# ERpcukSD.net
KiCad netlist of a schematic drawn in EAGLE
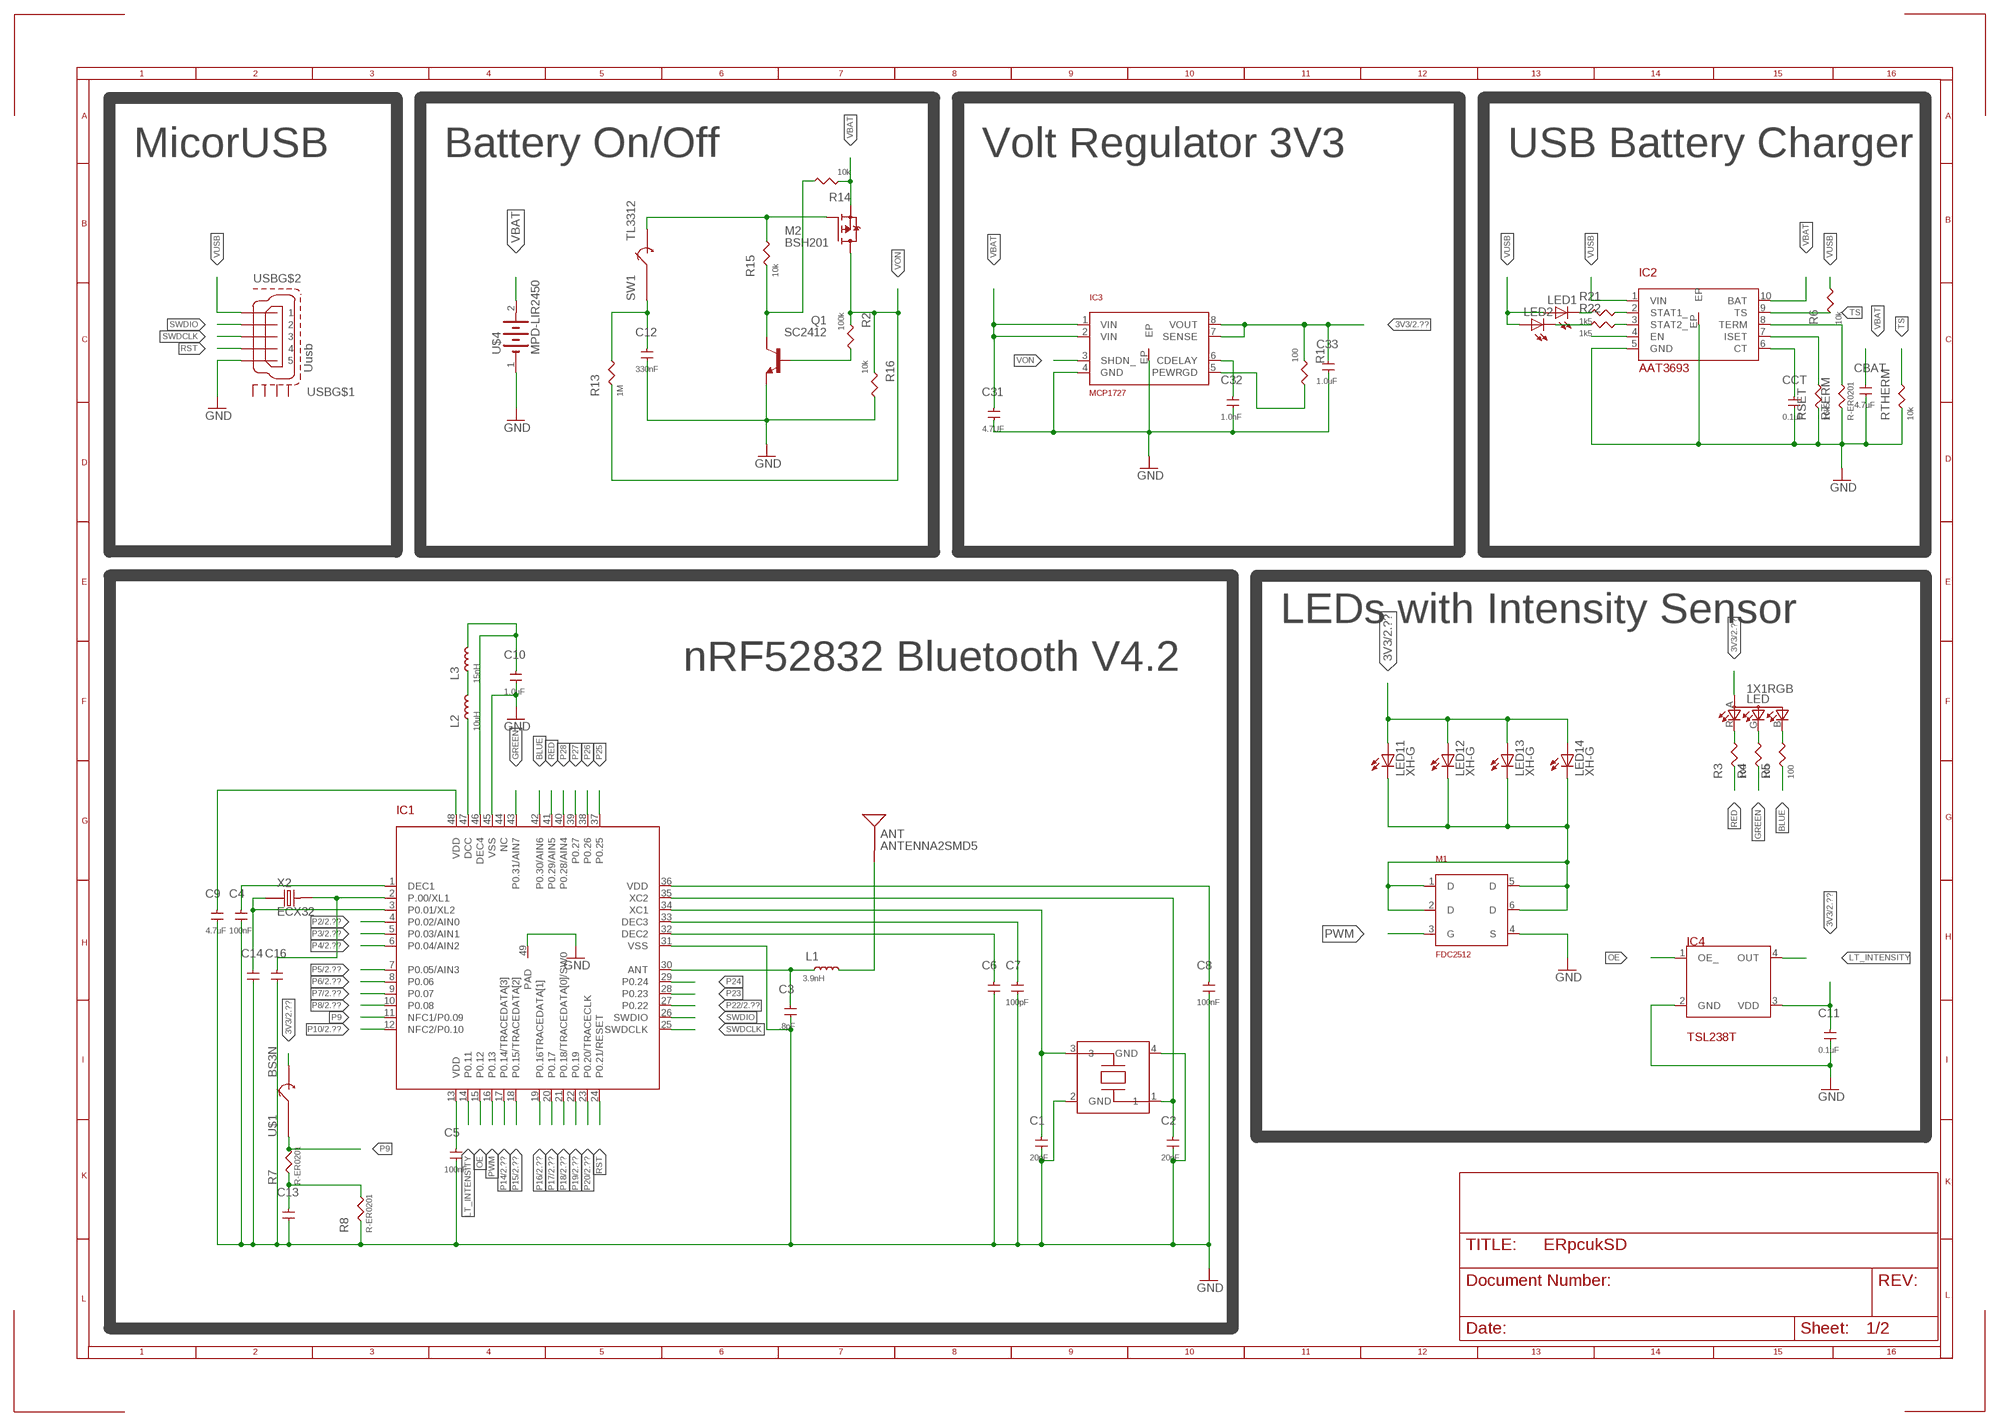
[diagram p0: schematic, sheet 1]
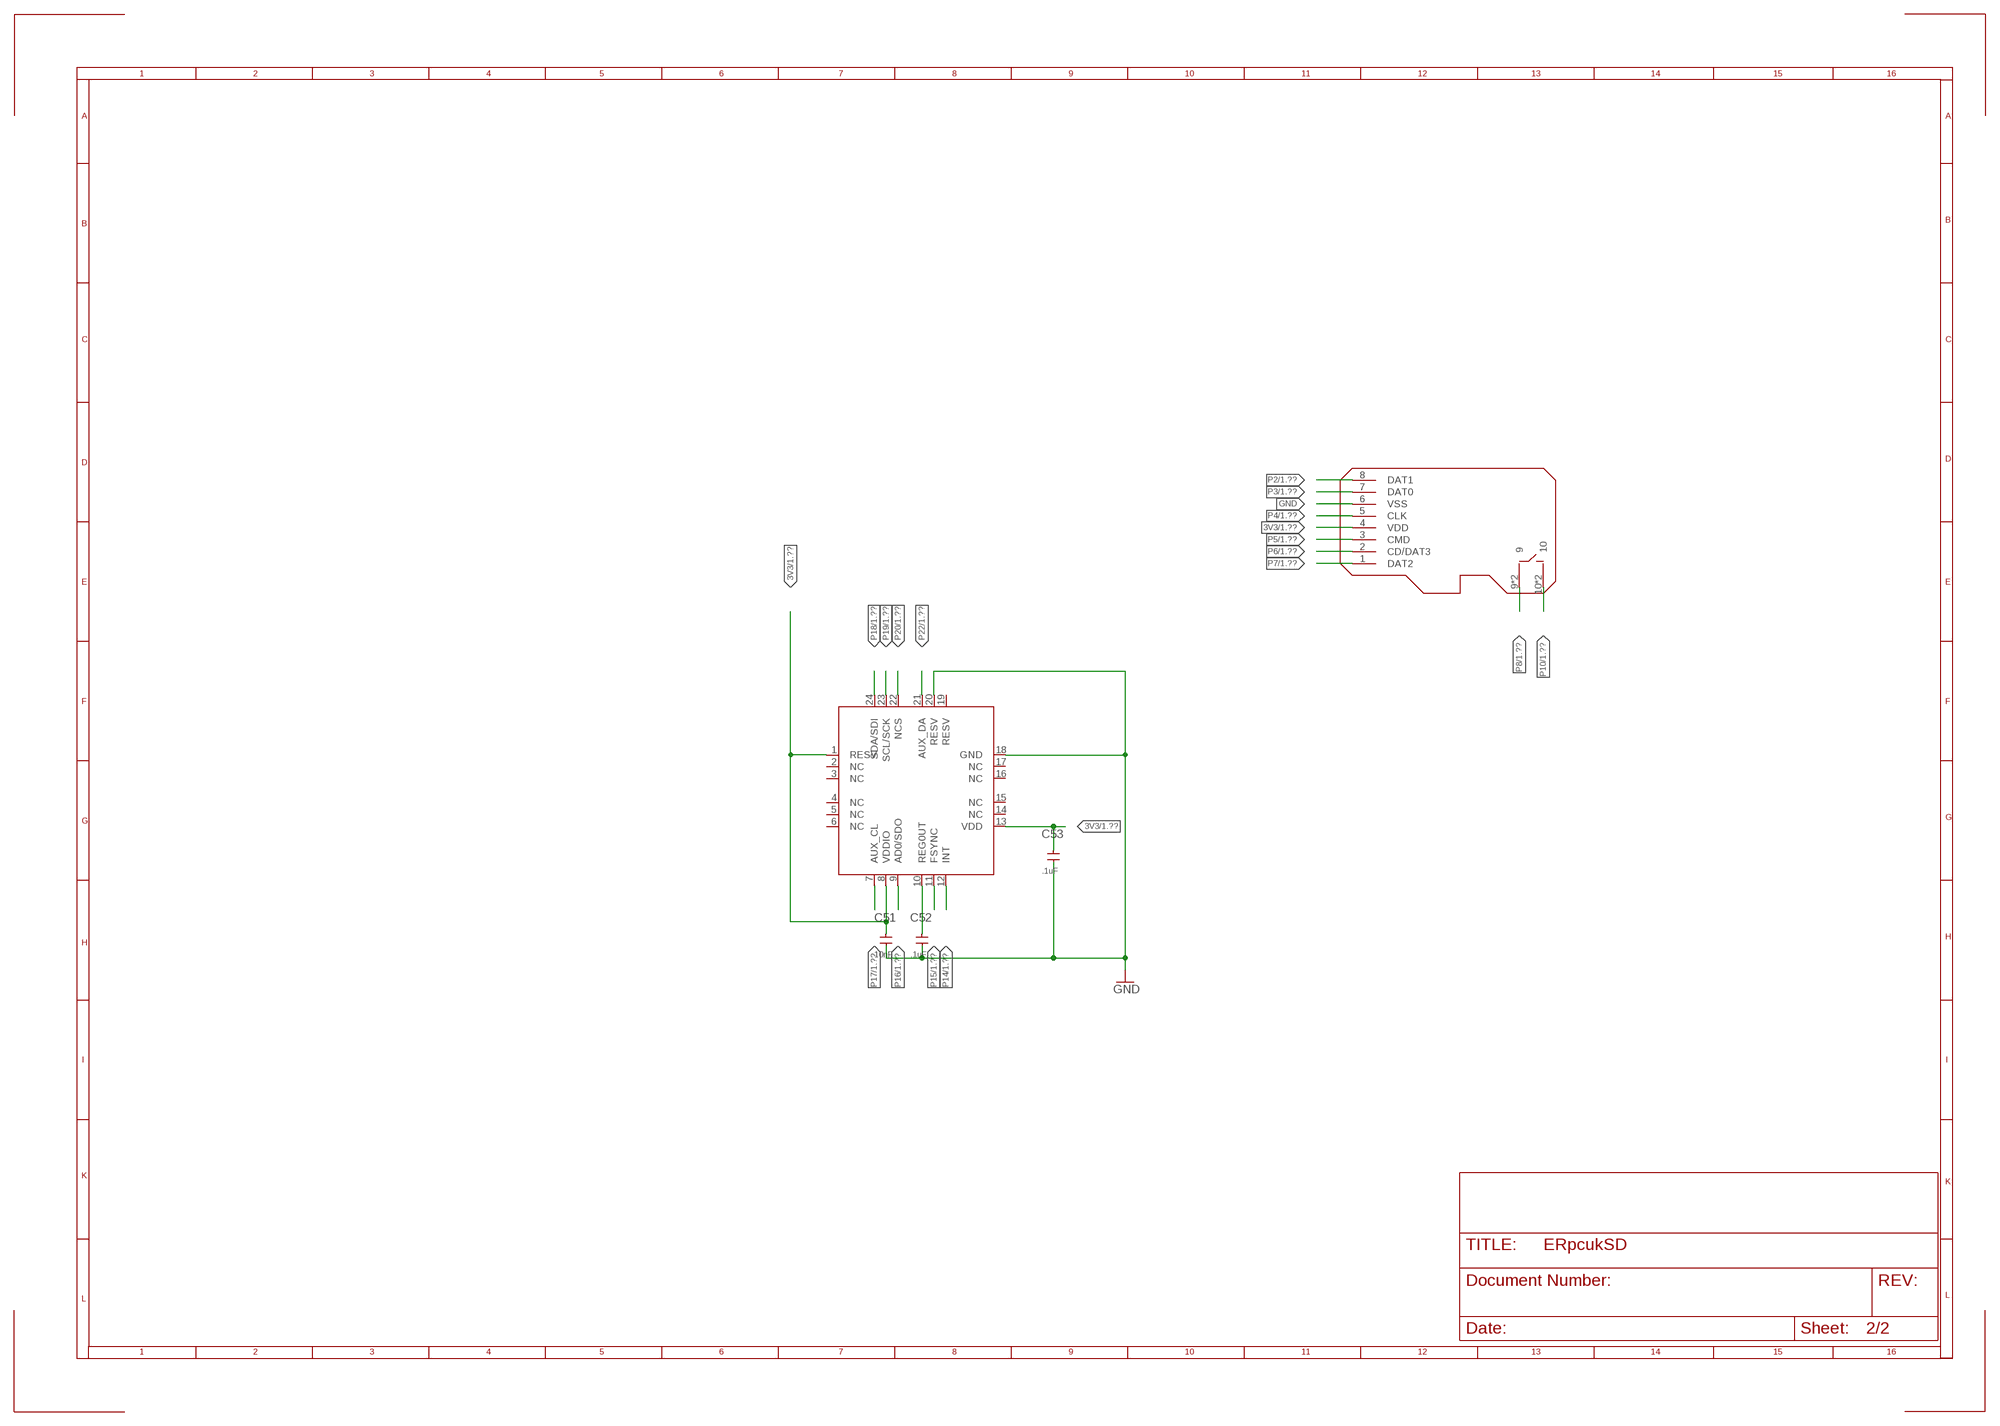
[diagram p1: schematic, sheet 2]

(export (version "E")
  (design (tool "Eeschema 10.0.6"))
  (components
    (comp (ref "C51")
      (value "10nF")
      (footprint "eagle-import:C0201")
      (libsource (lib "eagle-import") (part "C-ER201"))
    )
    (comp (ref "C52")
      (value ".1uF")
      (footprint "eagle-import:C0201")
      (libsource (lib "eagle-import") (part "C-ER201"))
    )
    (comp (ref "C53")
      (value ".1uF")
      (footprint "eagle-import:C0201")
      (libsource (lib "eagle-import") (part "C-ER201"))
    )
    (comp (ref "IC5")
      (value "MPU9250")
      (footprint "eagle-import:3X3_24_QFN_CORRECTED")
      (libsource (lib "eagle-import") (part "MPU9250_CORRECTED"))
    )
    (comp (ref "U$2")
      (value "MICROSD")
      (footprint "eagle-import:MICROSD")
      (libsource (lib "eagle-import") (part "MICROSD"))
    )
    (comp (ref "ANT")
      (value "ANTENNA2SMD5")
      (footprint "eagle-import:ANTENNA-CHIP5")
      (libsource (lib "eagle-import") (part "ANTENNA2SMD5"))
    )
    (comp (ref "C1")
      (value "20pF")
      (footprint "eagle-import:C0201")
      (libsource (lib "eagle-import") (part "C-ER201"))
    )
    (comp (ref "C2")
      (value "20pF")
      (footprint "eagle-import:C0201")
      (libsource (lib "eagle-import") (part "C-ER201"))
    )
    (comp (ref "C3")
      (value ".8pF")
      (footprint "eagle-import:C0201")
      (libsource (lib "eagle-import") (part "C-ER201"))
    )
    (comp (ref "C4")
      (value "100nF")
      (footprint "eagle-import:C0201")
      (libsource (lib "eagle-import") (part "C-ER201"))
    )
    (comp (ref "C5")
      (value "100nF")
      (footprint "eagle-import:C0201")
      (libsource (lib "eagle-import") (part "C-ER201"))
    )
    (comp (ref "C6")
      (value "C-ER201")
      (footprint "eagle-import:C0201")
      (libsource (lib "eagle-import") (part "C-ER201"))
    )
    (comp (ref "C7")
      (value "100pF")
      (footprint "eagle-import:C0201")
      (libsource (lib "eagle-import") (part "C-ER201"))
    )
    (comp (ref "C8")
      (value "100nF")
      (footprint "eagle-import:C0201")
      (libsource (lib "eagle-import") (part "C-ER201"))
    )
    (comp (ref "C9")
      (value "4.7uF")
      (footprint "eagle-import:C0402")
      (libsource (lib "eagle-import") (part "C-ERC0402"))
    )
    (comp (ref "C10")
      (value "1.0uF")
      (footprint "eagle-import:C0201")
      (libsource (lib "eagle-import") (part "C-ER201"))
    )
    (comp (ref "C11")
      (value "0.1uF")
      (footprint "eagle-import:C0201")
      (libsource (lib "eagle-import") (part "C-ER201"))
    )
    (comp (ref "C12")
      (value "330nF")
      (footprint "eagle-import:C0201")
      (libsource (lib "eagle-import") (part "C-ER201"))
    )
    (comp (ref "C13")
      (value "C-ER201")
      (footprint "eagle-import:C0201")
      (libsource (lib "eagle-import") (part "C-ER201"))
    )
    (comp (ref "C14")
      (value "C-ER201")
      (footprint "eagle-import:C0201")
      (libsource (lib "eagle-import") (part "C-ER201"))
    )
    (comp (ref "C16")
      (value "C-ER201")
      (footprint "eagle-import:C0201")
      (libsource (lib "eagle-import") (part "C-ER201"))
    )
    (comp (ref "C31")
      (value "4.7UF")
      (footprint "eagle-import:C0402")
      (libsource (lib "eagle-import") (part "C-ERC0402"))
    )
    (comp (ref "C32")
      (value "1.0nF")
      (footprint "eagle-import:C0201")
      (libsource (lib "eagle-import") (part "C-ER201"))
    )
    (comp (ref "C33")
      (value "1.0uF")
      (footprint "eagle-import:C0201")
      (libsource (lib "eagle-import") (part "C-ER201"))
    )
    (comp (ref "CBAT")
      (value "4.7uF")
      (footprint "eagle-import:C0402")
      (libsource (lib "eagle-import") (part "C-ERC0402"))
    )
    (comp (ref "CCT")
      (value "0.1uF")
      (footprint "eagle-import:C0201")
      (libsource (lib "eagle-import") (part "C-ER201"))
    )
    (comp (ref "IC1")
      (value "NRF52832")
      (footprint "eagle-import:QFN48")
      (libsource (lib "eagle-import") (part "NRF52832"))
    )
    (comp (ref "IC2")
      (value "AAT3693")
      (footprint "eagle-import:AAT3693")
      (libsource (lib "eagle-import") (part "AAT3693"))
    )
    (comp (ref "IC3")
      (value "MCP1727")
      (footprint "eagle-import:DFN8-3X3")
      (libsource (lib "eagle-import") (part "MCP1727"))
    )
    (comp (ref "IC4")
      (value "TSL238T")
      (footprint "eagle-import:T4")
      (libsource (lib "eagle-import") (part "TSL238T"))
    )
    (comp (ref "L1")
      (value "3.9nH")
      (footprint "eagle-import:C0201")
      (libsource (lib "eagle-import") (part "L-ER0201"))
    )
    (comp (ref "L2")
      (value "10uH")
      (footprint "eagle-import:R0603")
      (libsource (lib "eagle-import") (part "L-ERL603"))
    )
    (comp (ref "L3")
      (value "15nH")
      (footprint "eagle-import:C0201")
      (libsource (lib "eagle-import") (part "L-ER0201"))
    )
    (comp (ref "LED")
      (value "1X1RGB")
      (footprint "eagle-import:1X1")
      (libsource (lib "eagle-import") (part "1X1RGB"))
    )
    (comp (ref "LED1")
      (value "LEDCHIP-LED0603")
      (footprint "eagle-import:CHIP-LED0603")
      (libsource (lib "eagle-import") (part "LEDCHIP-LED0603"))
    )
    (comp (ref "LED2")
      (value "LEDCHIP-LED0603")
      (footprint "eagle-import:CHIP-LED0603")
      (libsource (lib "eagle-import") (part "LEDCHIP-LED0603"))
    )
    (comp (ref "LED11")
      (value "XH-G")
      (footprint "eagle-import:XH-G")
      (libsource (lib "eagle-import") (part "XH-G"))
    )
    (comp (ref "LED12")
      (value "XH-G")
      (footprint "eagle-import:XH-G")
      (libsource (lib "eagle-import") (part "XH-G"))
    )
    (comp (ref "LED13")
      (value "XH-G")
      (footprint "eagle-import:XH-G")
      (libsource (lib "eagle-import") (part "XH-G"))
    )
    (comp (ref "LED14")
      (value "XH-G")
      (footprint "eagle-import:XH-G")
      (libsource (lib "eagle-import") (part "XH-G"))
    )
    (comp (ref "M1")
      (value "FDC2512")
      (footprint "eagle-import:SSOT6")
      (libsource (lib "eagle-import") (part "FDC2512"))
    )
    (comp (ref "M2")
      (value "BSH201")
      (footprint "eagle-import:SOT23")
      (libsource (lib "eagle-import") (part "BSH201"))
    )
    (comp (ref "Q1")
      (value "SC2412")
      (footprint "eagle-import:SC59-BEC")
      (libsource (lib "eagle-import") (part "SC2412"))
    )
    (comp (ref "R1")
      (value "100")
      (footprint "eagle-import:R0201")
      (libsource (lib "eagle-import") (part "R-ER0201"))
    )
    (comp (ref "R2")
      (value "100k")
      (footprint "eagle-import:R0201")
      (libsource (lib "eagle-import") (part "R-ER0201"))
    )
    (comp (ref "R3")
      (value "100")
      (footprint "eagle-import:R0201")
      (libsource (lib "eagle-import") (part "R-ER0201"))
    )
    (comp (ref "R4")
      (value "100")
      (footprint "eagle-import:R0201")
      (libsource (lib "eagle-import") (part "R-ER0201"))
    )
    (comp (ref "R5")
      (value "100")
      (footprint "eagle-import:R0201")
      (libsource (lib "eagle-import") (part "R-ER0201"))
    )
    (comp (ref "R6")
      (value "10k")
      (footprint "eagle-import:R0201")
      (libsource (lib "eagle-import") (part "R-ER0201"))
    )
    (comp (ref "R7")
      (value "R-ER0201")
      (footprint "eagle-import:R0201")
      (libsource (lib "eagle-import") (part "R-ER0201"))
    )
    (comp (ref "R8")
      (value "R-ER0201")
      (footprint "eagle-import:R0201")
      (libsource (lib "eagle-import") (part "R-ER0201"))
    )
    (comp (ref "R13")
      (value "1M")
      (footprint "eagle-import:R0201")
      (libsource (lib "eagle-import") (part "R-ER0201"))
    )
    (comp (ref "R14")
      (value "10k")
      (footprint "eagle-import:R0201")
      (libsource (lib "eagle-import") (part "R-ER0201"))
    )
    (comp (ref "R15")
      (value "10k")
      (footprint "eagle-import:R0201")
      (libsource (lib "eagle-import") (part "R-ER0201"))
    )
    (comp (ref "R16")
      (value "10k")
      (footprint "eagle-import:R0201")
      (libsource (lib "eagle-import") (part "R-ER0201"))
    )
    (comp (ref "R21")
      (value "1k5")
      (footprint "eagle-import:R0201")
      (libsource (lib "eagle-import") (part "R-ER0201"))
    )
    (comp (ref "R22")
      (value "1k5")
      (footprint "eagle-import:R0201")
      (libsource (lib "eagle-import") (part "R-ER0201"))
    )
    (comp (ref "RSET")
      (value "16k5")
      (footprint "eagle-import:R0201")
      (libsource (lib "eagle-import") (part "R-ER0201"))
    )
    (comp (ref "RTERM")
      (value "R-ER0201")
      (footprint "eagle-import:R0201")
      (libsource (lib "eagle-import") (part "R-ER0201"))
    )
    (comp (ref "RTHERM")
      (value "10k")
      (footprint "eagle-import:R0201")
      (libsource (lib "eagle-import") (part "R-ER0201"))
    )
    (comp (ref "SW1")
      (value "TL3312")
      (footprint "eagle-import:TL3312")
      (libsource (lib "eagle-import") (part "TL3312"))
    )
    (comp (ref "U$1")
      (value "BS3N")
      (footprint "eagle-import:BS3N")
      (libsource (lib "eagle-import") (part "BS3N"))
    )
    (comp (ref "U$4")
      (value "MPD-LIR2450")
      (footprint "eagle-import:LIR2450")
      (libsource (lib "eagle-import") (part "MPD-LIR2450"))
    )
    (comp (ref "USB")
      (value "Uusb")
      (footprint "eagle-import:ZX62R-B-5P")
      (libsource (lib "eagle-import") (part "MICRO-USB-SHIELD-ZX62R-B-5P"))
    )
    (comp (ref "X1")
      (value "FA-128")
      (footprint "eagle-import:FA-128")
      (libsource (lib "eagle-import") (part "FA-128"))
    )
    (comp (ref "X2")
      (value "ECX32")
      (footprint "eagle-import:ECX39")
      (libsource (lib "eagle-import") (part "ECX32"))
    )
  )
  (nets
    (net (code "1") (name "3V3") (class "Default")
      (node (ref "C11") (pin "2") (pinfunction "P$2_2") (pintype "bidirectional"))
      (node (ref "C33") (pin "2") (pinfunction "P$2_2") (pintype "bidirectional"))
      (node (ref "C5") (pin "2") (pinfunction "P$2_2") (pintype "bidirectional"))
      (node (ref "C51") (pin "2") (pinfunction "P$2_2") (pintype "bidirectional"))
      (node (ref "C53") (pin "2") (pinfunction "P$2_2") (pintype "bidirectional"))
      (node (ref "C8") (pin "2") (pinfunction "P$2_2") (pintype "bidirectional"))
      (node (ref "C9") (pin "2") (pinfunction "P$2_2") (pintype "bidirectional"))
      (node (ref "IC1") (pin "13") (pinfunction "VDD_13") (pintype "bidirectional"))
      (node (ref "IC1") (pin "36") (pinfunction "VDD_36") (pintype "bidirectional"))
      (node (ref "IC1") (pin "48") (pinfunction "VDD_48") (pintype "bidirectional"))
      (node (ref "IC3") (pin "7") (pinfunction "SENSE_7") (pintype "bidirectional"))
      (node (ref "IC3") (pin "8") (pinfunction "VOUT_8") (pintype "bidirectional"))
      (node (ref "IC4") (pin "3") (pinfunction "VDD_3") (pintype "bidirectional"))
      (node (ref "IC5") (pin "1") (pinfunction "RESV_1") (pintype "bidirectional"))
      (node (ref "IC5") (pin "13") (pinfunction "VDD_13") (pintype "bidirectional"))
      (node (ref "IC5") (pin "8") (pinfunction "VDDIO_8") (pintype "bidirectional"))
      (node (ref "LED") (pin "A") (pinfunction "A2_A") (pintype "passive"))
      (node (ref "LED11") (pin "2") (pinfunction "A_2") (pintype "passive"))
      (node (ref "LED12") (pin "2") (pinfunction "A_2") (pintype "passive"))
      (node (ref "LED13") (pin "2") (pinfunction "A_2") (pintype "passive"))
      (node (ref "LED14") (pin "2") (pinfunction "A_2") (pintype "passive"))
      (node (ref "R1") (pin "1") (pinfunction "P$1_1") (pintype "bidirectional"))
      (node (ref "U$1") (pin "2") (pinfunction "2_2") (pintype "bidirectional"))
      (node (ref "U$2") (pin "4") (pinfunction "VDD_4") (pintype "bidirectional"))
    )
    (net (code "2") (name "BLUE") (class "Default")
      (node (ref "IC1") (pin "42") (pinfunction "P0.30/AIN6_42") (pintype "bidirectional"))
      (node (ref "R5") (pin "1") (pinfunction "P$1_1") (pintype "bidirectional"))
    )
    (net (code "3") (name "GND") (class "Default")
      (node (ref "C1") (pin "1") (pinfunction "P$1_1") (pintype "bidirectional"))
      (node (ref "C10") (pin "1") (pinfunction "P$1_1") (pintype "bidirectional"))
      (node (ref "C11") (pin "1") (pinfunction "P$1_1") (pintype "bidirectional"))
      (node (ref "C12") (pin "1") (pinfunction "P$1_1") (pintype "bidirectional"))
      (node (ref "C13") (pin "1") (pinfunction "P$1_1") (pintype "bidirectional"))
      (node (ref "C14") (pin "1") (pinfunction "P$1_1") (pintype "bidirectional"))
      (node (ref "C16") (pin "1") (pinfunction "P$1_1") (pintype "bidirectional"))
      (node (ref "C2") (pin "1") (pinfunction "P$1_1") (pintype "bidirectional"))
      (node (ref "C3") (pin "1") (pinfunction "P$1_1") (pintype "bidirectional"))
      (node (ref "C31") (pin "1") (pinfunction "P$1_1") (pintype "bidirectional"))
      (node (ref "C32") (pin "1") (pinfunction "P$1_1") (pintype "bidirectional"))
      (node (ref "C33") (pin "1") (pinfunction "P$1_1") (pintype "bidirectional"))
      (node (ref "C4") (pin "1") (pinfunction "P$1_1") (pintype "bidirectional"))
      (node (ref "C5") (pin "1") (pinfunction "P$1_1") (pintype "bidirectional"))
      (node (ref "C51") (pin "1") (pinfunction "P$1_1") (pintype "bidirectional"))
      (node (ref "C52") (pin "1") (pinfunction "P$1_1") (pintype "bidirectional"))
      (node (ref "C53") (pin "1") (pinfunction "P$1_1") (pintype "bidirectional"))
      (node (ref "C6") (pin "1") (pinfunction "P$1_1") (pintype "bidirectional"))
      (node (ref "C7") (pin "1") (pinfunction "P$1_1") (pintype "bidirectional"))
      (node (ref "C8") (pin "1") (pinfunction "P$1_1") (pintype "bidirectional"))
      (node (ref "C9") (pin "1") (pinfunction "P$1_1") (pintype "bidirectional"))
      (node (ref "CBAT") (pin "1") (pinfunction "P$1_1") (pintype "bidirectional"))
      (node (ref "CCT") (pin "1") (pinfunction "P$1_1") (pintype "bidirectional"))
      (node (ref "IC1") (pin "31") (pinfunction "VSS_31") (pintype "bidirectional"))
      (node (ref "IC1") (pin "45") (pinfunction "VSS_45") (pintype "bidirectional"))
      (node (ref "IC1") (pin "49") (pinfunction "PAD_49") (pintype "bidirectional"))
      (node (ref "IC2") (pin "5") (pinfunction "GND_5") (pintype "bidirectional"))
      (node (ref "IC2") (pin "EP") (pinfunction "EP_EP") (pintype "bidirectional"))
      (node (ref "IC3") (pin "4") (pinfunction "GND_4") (pintype "bidirectional"))
      (node (ref "IC3") (pin "EP") (pinfunction "EP_EP") (pintype "bidirectional"))
      (node (ref "IC4") (pin "2") (pinfunction "GND_2") (pintype "bidirectional"))
      (node (ref "IC5") (pin "18") (pinfunction "GND_18") (pintype "bidirectional"))
      (node (ref "IC5") (pin "20") (pinfunction "RESV_20") (pintype "bidirectional"))
      (node (ref "M1") (pin "4") (pinfunction "S_4") (pintype "bidirectional"))
      (node (ref "Q1") (pin "E") (pinfunction "E_E") (pintype "passive"))
      (node (ref "R16") (pin "2") (pinfunction "P$2_2") (pintype "bidirectional"))
      (node (ref "R8") (pin "1") (pinfunction "P$1_1") (pintype "bidirectional"))
      (node (ref "RSET") (pin "1") (pinfunction "P$1_1") (pintype "bidirectional"))
      (node (ref "RTERM") (pin "1") (pinfunction "P$1_1") (pintype "bidirectional"))
      (node (ref "RTHERM") (pin "1") (pinfunction "P$1_1") (pintype "bidirectional"))
      (node (ref "U$2") (pin "6") (pinfunction "VSS_6") (pintype "bidirectional"))
      (node (ref "U$4") (pin "1") (pinfunction "-_1") (pintype "passive"))
      (node (ref "USB") (pin "1") (pinfunction "5_1") (pintype "input"))
      (node (ref "X1") (pin "2") (pinfunction "GND_2") (pintype "bidirectional"))
      (node (ref "X1") (pin "4") (pinfunction "GND_4") (pintype "bidirectional"))
    )
    (net (code "4") (name "GREEN") (class "Default")
      (node (ref "IC1") (pin "43") (pinfunction "P0.31/AIN7_43") (pintype "bidirectional"))
      (node (ref "R4") (pin "1") (pinfunction "P$1_1") (pintype "bidirectional"))
    )
    (net (code "5") (name "LT_INTENSITY") (class "Default")
      (node (ref "IC1") (pin "14") (pinfunction "P0.11_14") (pintype "bidirectional"))
      (node (ref "IC4") (pin "4") (pinfunction "OUT_4") (pintype "bidirectional"))
    )
    (net (code "6") (name "Net-(ANT-SIGNAL)") (class "Default")
      (node (ref "ANT") (pin "FEED") (pinfunction "SIGNAL_FEED") (pintype "bidirectional"))
      (node (ref "L1") (pin "2") (pinfunction "P$2_2") (pintype "bidirectional"))
    )
    (net (code "7") (name "Net-(C1-P$2)") (class "Default")
      (node (ref "C1") (pin "2") (pinfunction "P$2_2") (pintype "bidirectional"))
      (node (ref "IC1") (pin "34") (pinfunction "XC1_34") (pintype "bidirectional"))
      (node (ref "X1") (pin "3") (pinfunction "3_3") (pintype "bidirectional"))
    )
    (net (code "8") (name "Net-(C2-P$2)") (class "Default")
      (node (ref "C2") (pin "2") (pinfunction "P$2_2") (pintype "bidirectional"))
      (node (ref "IC1") (pin "35") (pinfunction "XC2_35") (pintype "bidirectional"))
      (node (ref "X1") (pin "1") (pinfunction "1_1") (pintype "bidirectional"))
    )
    (net (code "9") (name "Net-(C3-P$2)") (class "Default")
      (node (ref "C3") (pin "2") (pinfunction "P$2_2") (pintype "bidirectional"))
      (node (ref "IC1") (pin "30") (pinfunction "ANT_30") (pintype "bidirectional"))
      (node (ref "L1") (pin "1") (pinfunction "P$1_1") (pintype "bidirectional"))
    )
    (net (code "10") (name "Net-(C4-P$2)") (class "Default")
      (node (ref "C4") (pin "2") (pinfunction "P$2_2") (pintype "bidirectional"))
      (node (ref "IC1") (pin "1") (pinfunction "DEC1_1") (pintype "bidirectional"))
    )
    (net (code "11") (name "Net-(C6-P$2)") (class "Default")
      (node (ref "C6") (pin "2") (pinfunction "P$2_2") (pintype "bidirectional"))
      (node (ref "IC1") (pin "32") (pinfunction "DEC2_32") (pintype "bidirectional"))
    )
    (net (code "12") (name "Net-(C7-P$2)") (class "Default")
      (node (ref "C7") (pin "2") (pinfunction "P$2_2") (pintype "bidirectional"))
      (node (ref "IC1") (pin "33") (pinfunction "DEC3_33") (pintype "bidirectional"))
    )
    (net (code "13") (name "Net-(C10-P$2)") (class "Default")
      (node (ref "C10") (pin "2") (pinfunction "P$2_2") (pintype "bidirectional"))
      (node (ref "IC1") (pin "46") (pinfunction "DEC4_46") (pintype "bidirectional"))
      (node (ref "L3") (pin "2") (pinfunction "P$2_2") (pintype "bidirectional"))
    )
    (net (code "14") (name "Net-(C12-P$2)") (class "Default")
      (node (ref "C12") (pin "2") (pinfunction "P$2_2") (pintype "bidirectional"))
      (node (ref "R13") (pin "2") (pinfunction "P$2_2") (pintype "bidirectional"))
      (node (ref "SW1") (pin "1") (pinfunction "1_1") (pintype "bidirectional"))
    )
    (net (code "15") (name "Net-(C13-P$2)") (class "Default")
      (node (ref "C13") (pin "2") (pinfunction "P$2_2") (pintype "bidirectional"))
      (node (ref "R7") (pin "1") (pinfunction "P$1_1") (pintype "bidirectional"))
      (node (ref "R8") (pin "2") (pinfunction "P$2_2") (pintype "bidirectional"))
    )
    (net (code "16") (name "Net-(C14-P$2)") (class "Default")
      (node (ref "C14") (pin "2") (pinfunction "P$2_2") (pintype "bidirectional"))
      (node (ref "IC1") (pin "3") (pinfunction "P0.01/XL2_3") (pintype "bidirectional"))
      (node (ref "X2") (pin "P$1") (pinfunction "1_P$1") (pintype "passive"))
    )
    (net (code "17") (name "Net-(C16-P$2)") (class "Default")
      (node (ref "C16") (pin "2") (pinfunction "P$2_2") (pintype "bidirectional"))
      (node (ref "IC1") (pin "2") (pinfunction "P.00/XL1_2") (pintype "bidirectional"))
      (node (ref "X2") (pin "P$2") (pinfunction "2_P$2") (pintype "passive"))
    )
    (net (code "18") (name "Net-(C32-P$2)") (class "Default")
      (node (ref "C32") (pin "2") (pinfunction "P$2_2") (pintype "bidirectional"))
      (node (ref "IC3") (pin "6") (pinfunction "CDELAY_6") (pintype "bidirectional"))
    )
    (net (code "19") (name "Net-(C52-P$2)") (class "Default")
      (node (ref "C52") (pin "2") (pinfunction "P$2_2") (pintype "bidirectional"))
      (node (ref "IC5") (pin "10") (pinfunction "REG0UT_10") (pintype "bidirectional"))
    )
    (net (code "20") (name "Net-(CCT-P$2)") (class "Default")
      (node (ref "CCT") (pin "2") (pinfunction "P$2_2") (pintype "bidirectional"))
      (node (ref "IC2") (pin "6") (pinfunction "CT_6") (pintype "bidirectional"))
    )
    (net (code "21") (name "Net-(IC1-DCC)") (class "Default")
      (node (ref "IC1") (pin "47") (pinfunction "DCC_47") (pintype "bidirectional"))
      (node (ref "L2") (pin "1") (pinfunction "P$1_1") (pintype "bidirectional"))
    )
    (net (code "22") (name "Net-(IC2-ISET)") (class "Default")
      (node (ref "IC2") (pin "7") (pinfunction "ISET_7") (pintype "bidirectional"))
      (node (ref "RSET") (pin "2") (pinfunction "P$2_2") (pintype "bidirectional"))
    )
    (net (code "23") (name "Net-(IC2-STAT1_)") (class "Default")
      (node (ref "IC2") (pin "2") (pinfunction "STAT1__2") (pintype "bidirectional"))
      (node (ref "R21") (pin "2") (pinfunction "P$2_2") (pintype "bidirectional"))
    )
    (net (code "24") (name "Net-(IC2-STAT2_)") (class "Default")
      (node (ref "IC2") (pin "3") (pinfunction "STAT2__3") (pintype "bidirectional"))
      (node (ref "R22") (pin "2") (pinfunction "P$2_2") (pintype "bidirectional"))
    )
    (net (code "25") (name "Net-(IC2-TERM)") (class "Default")
      (node (ref "IC2") (pin "8") (pinfunction "TERM_8") (pintype "bidirectional"))
      (node (ref "RTERM") (pin "2") (pinfunction "P$2_2") (pintype "bidirectional"))
    )
    (net (code "26") (name "Net-(IC3-PEWRGD)") (class "Default")
      (node (ref "IC3") (pin "5") (pinfunction "PEWRGD_5") (pintype "bidirectional"))
      (node (ref "R1") (pin "2") (pinfunction "P$2_2") (pintype "bidirectional"))
    )
    (net (code "27") (name "Net-(L2-P$2)") (class "Default")
      (node (ref "L2") (pin "2") (pinfunction "P$2_2") (pintype "bidirectional"))
      (node (ref "L3") (pin "1") (pinfunction "P$1_1") (pintype "bidirectional"))
    )
    (net (code "28") (name "Net-(LED-CBLUE)") (class "Default")
      (node (ref "LED") (pin "G") (pinfunction "CBLUE_G") (pintype "passive"))
      (node (ref "R4") (pin "2") (pinfunction "P$2_2") (pintype "bidirectional"))
    )
    (net (code "29") (name "Net-(LED-CGREEN)") (class "Default")
      (node (ref "LED") (pin "B") (pinfunction "CGREEN_B") (pintype "passive"))
      (node (ref "R5") (pin "2") (pinfunction "P$2_2") (pintype "bidirectional"))
    )
    (net (code "30") (name "Net-(LED-CRED)") (class "Default")
      (node (ref "LED") (pin "R") (pinfunction "CRED_R") (pintype "passive"))
      (node (ref "R3") (pin "2") (pinfunction "P$2_2") (pintype "bidirectional"))
    )
    (net (code "31") (name "Net-(LED11-C)") (class "Default")
      (node (ref "LED11") (pin "1") (pinfunction "C_1") (pintype "passive"))
      (node (ref "LED12") (pin "1") (pinfunction "C_1") (pintype "passive"))
      (node (ref "LED13") (pin "1") (pinfunction "C_1") (pintype "passive"))
      (node (ref "LED14") (pin "1") (pinfunction "C_1") (pintype "passive"))
      (node (ref "M1") (pin "1") (pinfunction "D_1") (pintype "bidirectional"))
      (node (ref "M1") (pin "2") (pinfunction "D_2") (pintype "bidirectional"))
      (node (ref "M1") (pin "5") (pinfunction "D_5") (pintype "bidirectional"))
      (node (ref "M1") (pin "6") (pinfunction "D_6") (pintype "bidirectional"))
    )
    (net (code "32") (name "Net-(M2-G)") (class "Default")
      (node (ref "M2") (pin "1") (pinfunction "G_1") (pintype "passive"))
      (node (ref "R15") (pin "2") (pinfunction "P$2_2") (pintype "bidirectional"))
      (node (ref "SW1") (pin "3") (pinfunction "2_3") (pintype "bidirectional"))
    )
    (net (code "33") (name "Net-(R2-P$2)") (class "Default")
      (node (ref "Q1") (pin "B") (pinfunction "B_B") (pintype "passive"))
      (node (ref "R2") (pin "2") (pinfunction "P$2_2") (pintype "bidirectional"))
    )
    (net (code "34") (name "Net-(R14-P$2)") (class "Default")
      (node (ref "Q1") (pin "C") (pinfunction "C_C") (pintype "passive"))
      (node (ref "R14") (pin "2") (pinfunction "P$2_2") (pintype "bidirectional"))
      (node (ref "R15") (pin "1") (pinfunction "P$1_1") (pintype "bidirectional"))
    )
    (net (code "35") (name "Net-(R21-P$1)") (class "Default")
      (node (ref "LED1") (pin "C") (pinfunction "C_C") (pintype "passive"))
      (node (ref "R21") (pin "1") (pinfunction "P$1_1") (pintype "bidirectional"))
    )
    (net (code "36") (name "Net-(R22-P$1)") (class "Default")
      (node (ref "LED2") (pin "C") (pinfunction "C_C") (pintype "passive"))
      (node (ref "R22") (pin "1") (pinfunction "P$1_1") (pintype "bidirectional"))
    )
    (net (code "37") (name "OE") (class "Default")
      (node (ref "IC1") (pin "15") (pinfunction "P0.12_15") (pintype "bidirectional"))
      (node (ref "IC4") (pin "1") (pinfunction "OE__1") (pintype "bidirectional"))
    )
    (net (code "38") (name "P2") (class "Default")
      (node (ref "IC1") (pin "4") (pinfunction "P0.02/AIN0_4") (pintype "bidirectional"))
      (node (ref "U$2") (pin "8") (pinfunction "DAT1_8") (pintype "bidirectional"))
    )
    (net (code "39") (name "P3") (class "Default")
      (node (ref "IC1") (pin "5") (pinfunction "P0.03/AIN1_5") (pintype "bidirectional"))
      (node (ref "U$2") (pin "7") (pinfunction "DAT0_7") (pintype "bidirectional"))
    )
    (net (code "40") (name "P4") (class "Default")
      (node (ref "IC1") (pin "6") (pinfunction "P0.04/AIN2_6") (pintype "bidirectional"))
      (node (ref "U$2") (pin "5") (pinfunction "CLK_5") (pintype "bidirectional"))
    )
    (net (code "41") (name "P5") (class "Default")
      (node (ref "IC1") (pin "7") (pinfunction "P0.05/AIN3_7") (pintype "bidirectional"))
      (node (ref "U$2") (pin "3") (pinfunction "CMD_3") (pintype "bidirectional"))
    )
    (net (code "42") (name "P6") (class "Default")
      (node (ref "IC1") (pin "8") (pinfunction "P0.06_8") (pintype "bidirectional"))
      (node (ref "U$2") (pin "2") (pinfunction "CD/DAT3_2") (pintype "bidirectional"))
    )
    (net (code "43") (name "P7") (class "Default")
      (node (ref "IC1") (pin "9") (pinfunction "P0.07_9") (pintype "bidirectional"))
      (node (ref "U$2") (pin "1") (pinfunction "DAT2_1") (pintype "bidirectional"))
    )
    (net (code "44") (name "P8") (class "Default")
      (node (ref "IC1") (pin "10") (pinfunction "P0.08_10") (pintype "bidirectional"))
      (node (ref "U$2") (pin "9") (pinfunction "9_9") (pintype "bidirectional"))
      (node (ref "U$2") (pin "9@1") (pinfunction "9_9@1") (pintype "bidirectional"))
    )
    (net (code "45") (name "P9") (class "Default")
      (node (ref "IC1") (pin "11") (pinfunction "NFC1/P0.09_11") (pintype "bidirectional"))
      (node (ref "R7") (pin "2") (pinfunction "P$2_2") (pintype "bidirectional"))
      (node (ref "U$1") (pin "1") (pinfunction "1_1") (pintype "bidirectional"))
    )
    (net (code "46") (name "P10") (class "Default")
      (node (ref "IC1") (pin "12") (pinfunction "NFC2/P0.10_12") (pintype "bidirectional"))
      (node (ref "U$2") (pin "10") (pinfunction "10_10") (pintype "bidirectional"))
      (node (ref "U$2") (pin "10@1") (pinfunction "10_10@1") (pintype "bidirectional"))
    )
    (net (code "47") (name "P14") (class "Default")
      (node (ref "IC1") (pin "17") (pinfunction "P0.14/TRACEDATA[3]_17") (pintype "bidirectional"))
      (node (ref "IC5") (pin "12") (pinfunction "INT_12") (pintype "bidirectional"))
    )
    (net (code "48") (name "P15") (class "Default")
      (node (ref "IC1") (pin "18") (pinfunction "P0.15/TRACEDATA[2]_18") (pintype "bidirectional"))
      (node (ref "IC5") (pin "11") (pinfunction "FSYNC_11") (pintype "bidirectional"))
    )
    (net (code "49") (name "P16") (class "Default")
      (node (ref "IC1") (pin "19") (pinfunction "P0.16TRACEDATA[1]_19") (pintype "bidirectional"))
      (node (ref "IC5") (pin "9") (pinfunction "AD0/SDO_9") (pintype "bidirectional"))
    )
    (net (code "50") (name "P17") (class "Default")
      (node (ref "IC1") (pin "20") (pinfunction "P0.17_20") (pintype "bidirectional"))
      (node (ref "IC5") (pin "7") (pinfunction "AUX_CL_7") (pintype "bidirectional"))
    )
    (net (code "51") (name "P18") (class "Default")
      (node (ref "IC1") (pin "21") (pinfunction "P0.18/TRACEDATA[0]/SW0_21") (pintype "bidirectional"))
      (node (ref "IC5") (pin "24") (pinfunction "SDA/SDI_24") (pintype "bidirectional"))
    )
    (net (code "52") (name "P19") (class "Default")
      (node (ref "IC1") (pin "22") (pinfunction "P0.19_22") (pintype "bidirectional"))
      (node (ref "IC5") (pin "23") (pinfunction "SCL/SCK_23") (pintype "bidirectional"))
    )
    (net (code "53") (name "P20") (class "Default")
      (node (ref "IC1") (pin "23") (pinfunction "P0.20/TRACECLK_23") (pintype "bidirectional"))
      (node (ref "IC5") (pin "22") (pinfunction "NCS_22") (pintype "bidirectional"))
    )
    (net (code "54") (name "P22") (class "Default")
      (node (ref "IC1") (pin "27") (pinfunction "P0.22_27") (pintype "bidirectional"))
      (node (ref "IC5") (pin "21") (pinfunction "AUX_DA_21") (pintype "bidirectional"))
    )
    (net (code "55") (name "P23") (class "Default")
      (node (ref "IC1") (pin "28") (pinfunction "P0.23_28") (pintype "bidirectional"))
    )
    (net (code "56") (name "P24") (class "Default")
      (node (ref "IC1") (pin "29") (pinfunction "P0.24_29") (pintype "bidirectional"))
    )
    (net (code "57") (name "P25") (class "Default")
      (node (ref "IC1") (pin "37") (pinfunction "P0.25_37") (pintype "bidirectional"))
    )
    (net (code "58") (name "P26") (class "Default")
      (node (ref "IC1") (pin "38") (pinfunction "P0.26_38") (pintype "bidirectional"))
    )
    (net (code "59") (name "P27") (class "Default")
      (node (ref "IC1") (pin "39") (pinfunction "P0.27_39") (pintype "bidirectional"))
    )
    (net (code "60") (name "P28") (class "Default")
      (node (ref "IC1") (pin "40") (pinfunction "P0.28/AIN4_40") (pintype "bidirectional"))
    )
    (net (code "61") (name "PWM") (class "Default")
      (node (ref "IC1") (pin "16") (pinfunction "P0.13_16") (pintype "bidirectional"))
      (node (ref "M1") (pin "3") (pinfunction "G_3") (pintype "bidirectional"))
    )
    (net (code "62") (name "RED") (class "Default")
      (node (ref "IC1") (pin "41") (pinfunction "P0.29/AIN5_41") (pintype "bidirectional"))
      (node (ref "R3") (pin "1") (pinfunction "P$1_1") (pintype "bidirectional"))
    )
    (net (code "63") (name "RST") (class "Default")
      (node (ref "IC1") (pin "24") (pinfunction "P0.21/RESET_24") (pintype "bidirectional"))
      (node (ref "USB") (pin "2") (pinfunction "4_2") (pintype "input"))
    )
    (net (code "64") (name "SWDCLK") (class "Default")
      (node (ref "IC1") (pin "25") (pinfunction "SWDCLK_25") (pintype "bidirectional"))
      (node (ref "USB") (pin "3") (pinfunction "3_3") (pintype "input"))
    )
    (net (code "65") (name "SWDIO") (class "Default")
      (node (ref "IC1") (pin "26") (pinfunction "SWDIO_26") (pintype "bidirectional"))
      (node (ref "USB") (pin "4") (pinfunction "2_4") (pintype "input"))
    )
    (net (code "66") (name "TS") (class "Default")
      (node (ref "IC2") (pin "9") (pinfunction "TS_9") (pintype "bidirectional"))
      (node (ref "R6") (pin "1") (pinfunction "P$1_1") (pintype "bidirectional"))
      (node (ref "RTHERM") (pin "2") (pinfunction "P$2_2") (pintype "bidirectional"))
    )
    (net (code "67") (name "VBAT") (class "Default")
      (node (ref "C31") (pin "2") (pinfunction "P$2_2") (pintype "bidirectional"))
      (node (ref "CBAT") (pin "2") (pinfunction "P$2_2") (pintype "bidirectional"))
      (node (ref "IC2") (pin "10") (pinfunction "BAT_10") (pintype "bidirectional"))
      (node (ref "IC3") (pin "1") (pinfunction "VIN_1") (pintype "bidirectional"))
      (node (ref "IC3") (pin "2") (pinfunction "VIN_2") (pintype "bidirectional"))
      (node (ref "M2") (pin "2") (pinfunction "S_2") (pintype "passive"))
      (node (ref "R14") (pin "1") (pinfunction "P$1_1") (pintype "bidirectional"))
      (node (ref "U$4") (pin "2") (pinfunction "+_2") (pintype "passive"))
    )
    (net (code "68") (name "VON") (class "Default")
      (node (ref "IC3") (pin "3") (pinfunction "SHDN__3") (pintype "bidirectional"))
      (node (ref "M2") (pin "3") (pinfunction "D_3") (pintype "passive"))
      (node (ref "R13") (pin "1") (pinfunction "P$1_1") (pintype "bidirectional"))
      (node (ref "R16") (pin "1") (pinfunction "P$1_1") (pintype "bidirectional"))
      (node (ref "R2") (pin "1") (pinfunction "P$1_1") (pintype "bidirectional"))
    )
    (net (code "69") (name "VUSB") (class "Default")
      (node (ref "IC2") (pin "1") (pinfunction "VIN_1") (pintype "bidirectional"))
      (node (ref "IC2") (pin "4") (pinfunction "EN_4") (pintype "bidirectional"))
      (node (ref "LED1") (pin "A") (pinfunction "A_A") (pintype "passive"))
      (node (ref "LED2") (pin "A") (pinfunction "A_A") (pintype "passive"))
      (node (ref "R6") (pin "2") (pinfunction "P$2_2") (pintype "bidirectional"))
      (node (ref "USB") (pin "5") (pinfunction "1_5") (pintype "input"))
    )
    (net (code "70") (name "unconnected-(IC1-NC-Pad44)") (class "Default")
      (node (ref "IC1") (pin "44") (pinfunction "NC_44") (pintype "bidirectional"))
    )
    (net (code "71") (name "unconnected-(IC5-NC-Pad2)") (class "Default")
      (node (ref "IC5") (pin "2") (pinfunction "NC_2") (pintype "bidirectional"))
    )
    (net (code "72") (name "unconnected-(IC5-NC-Pad3)") (class "Default")
      (node (ref "IC5") (pin "3") (pinfunction "NC_3") (pintype "bidirectional"))
    )
    (net (code "73") (name "unconnected-(IC5-NC-Pad4)") (class "Default")
      (node (ref "IC5") (pin "4") (pinfunction "NC_4") (pintype "bidirectional"))
    )
    (net (code "74") (name "unconnected-(IC5-NC-Pad5)") (class "Default")
      (node (ref "IC5") (pin "5") (pinfunction "NC_5") (pintype "bidirectional"))
    )
    (net (code "75") (name "unconnected-(IC5-NC-Pad6)") (class "Default")
      (node (ref "IC5") (pin "6") (pinfunction "NC_6") (pintype "bidirectional"))
    )
    (net (code "76") (name "unconnected-(IC5-NC-Pad14)") (class "Default")
      (node (ref "IC5") (pin "14") (pinfunction "NC_14") (pintype "bidirectional"))
    )
    (net (code "77") (name "unconnected-(IC5-NC-Pad15)") (class "Default")
      (node (ref "IC5") (pin "15") (pinfunction "NC_15") (pintype "bidirectional"))
    )
    (net (code "78") (name "unconnected-(IC5-NC-Pad16)") (class "Default")
      (node (ref "IC5") (pin "16") (pinfunction "NC_16") (pintype "bidirectional"))
    )
    (net (code "79") (name "unconnected-(IC5-NC-Pad17)") (class "Default")
      (node (ref "IC5") (pin "17") (pinfunction "NC_17") (pintype "bidirectional"))
    )
    (net (code "80") (name "unconnected-(IC5-RESV-Pad19)") (class "Default")
      (node (ref "IC5") (pin "19") (pinfunction "RESV_19") (pintype "bidirectional"))
    )
    (net (code "81") (name "unconnected-(USBA-S1-PadM1)") (class "Default")
      (node (ref "USB") (pin "M1") (pinfunction "S1_M1") (pintype "passive"))
    )
    (net (code "82") (name "unconnected-(USBA-S2-PadM2)") (class "Default")
      (node (ref "USB") (pin "M2") (pinfunction "S2_M2") (pintype "passive"))
    )
    (net (code "83") (name "unconnected-(USBA-S3-PadM3)") (class "Default")
      (node (ref "USB") (pin "M3") (pinfunction "S3_M3") (pintype "passive"))
    )
    (net (code "84") (name "unconnected-(USBA-S4-PadM4)") (class "Default")
      (node (ref "USB") (pin "M4") (pinfunction "S4_M4") (pintype "passive"))
    )
  )
)
